# CarteMere.net
KiCad netlist of a schematic drawn in Altium Designer
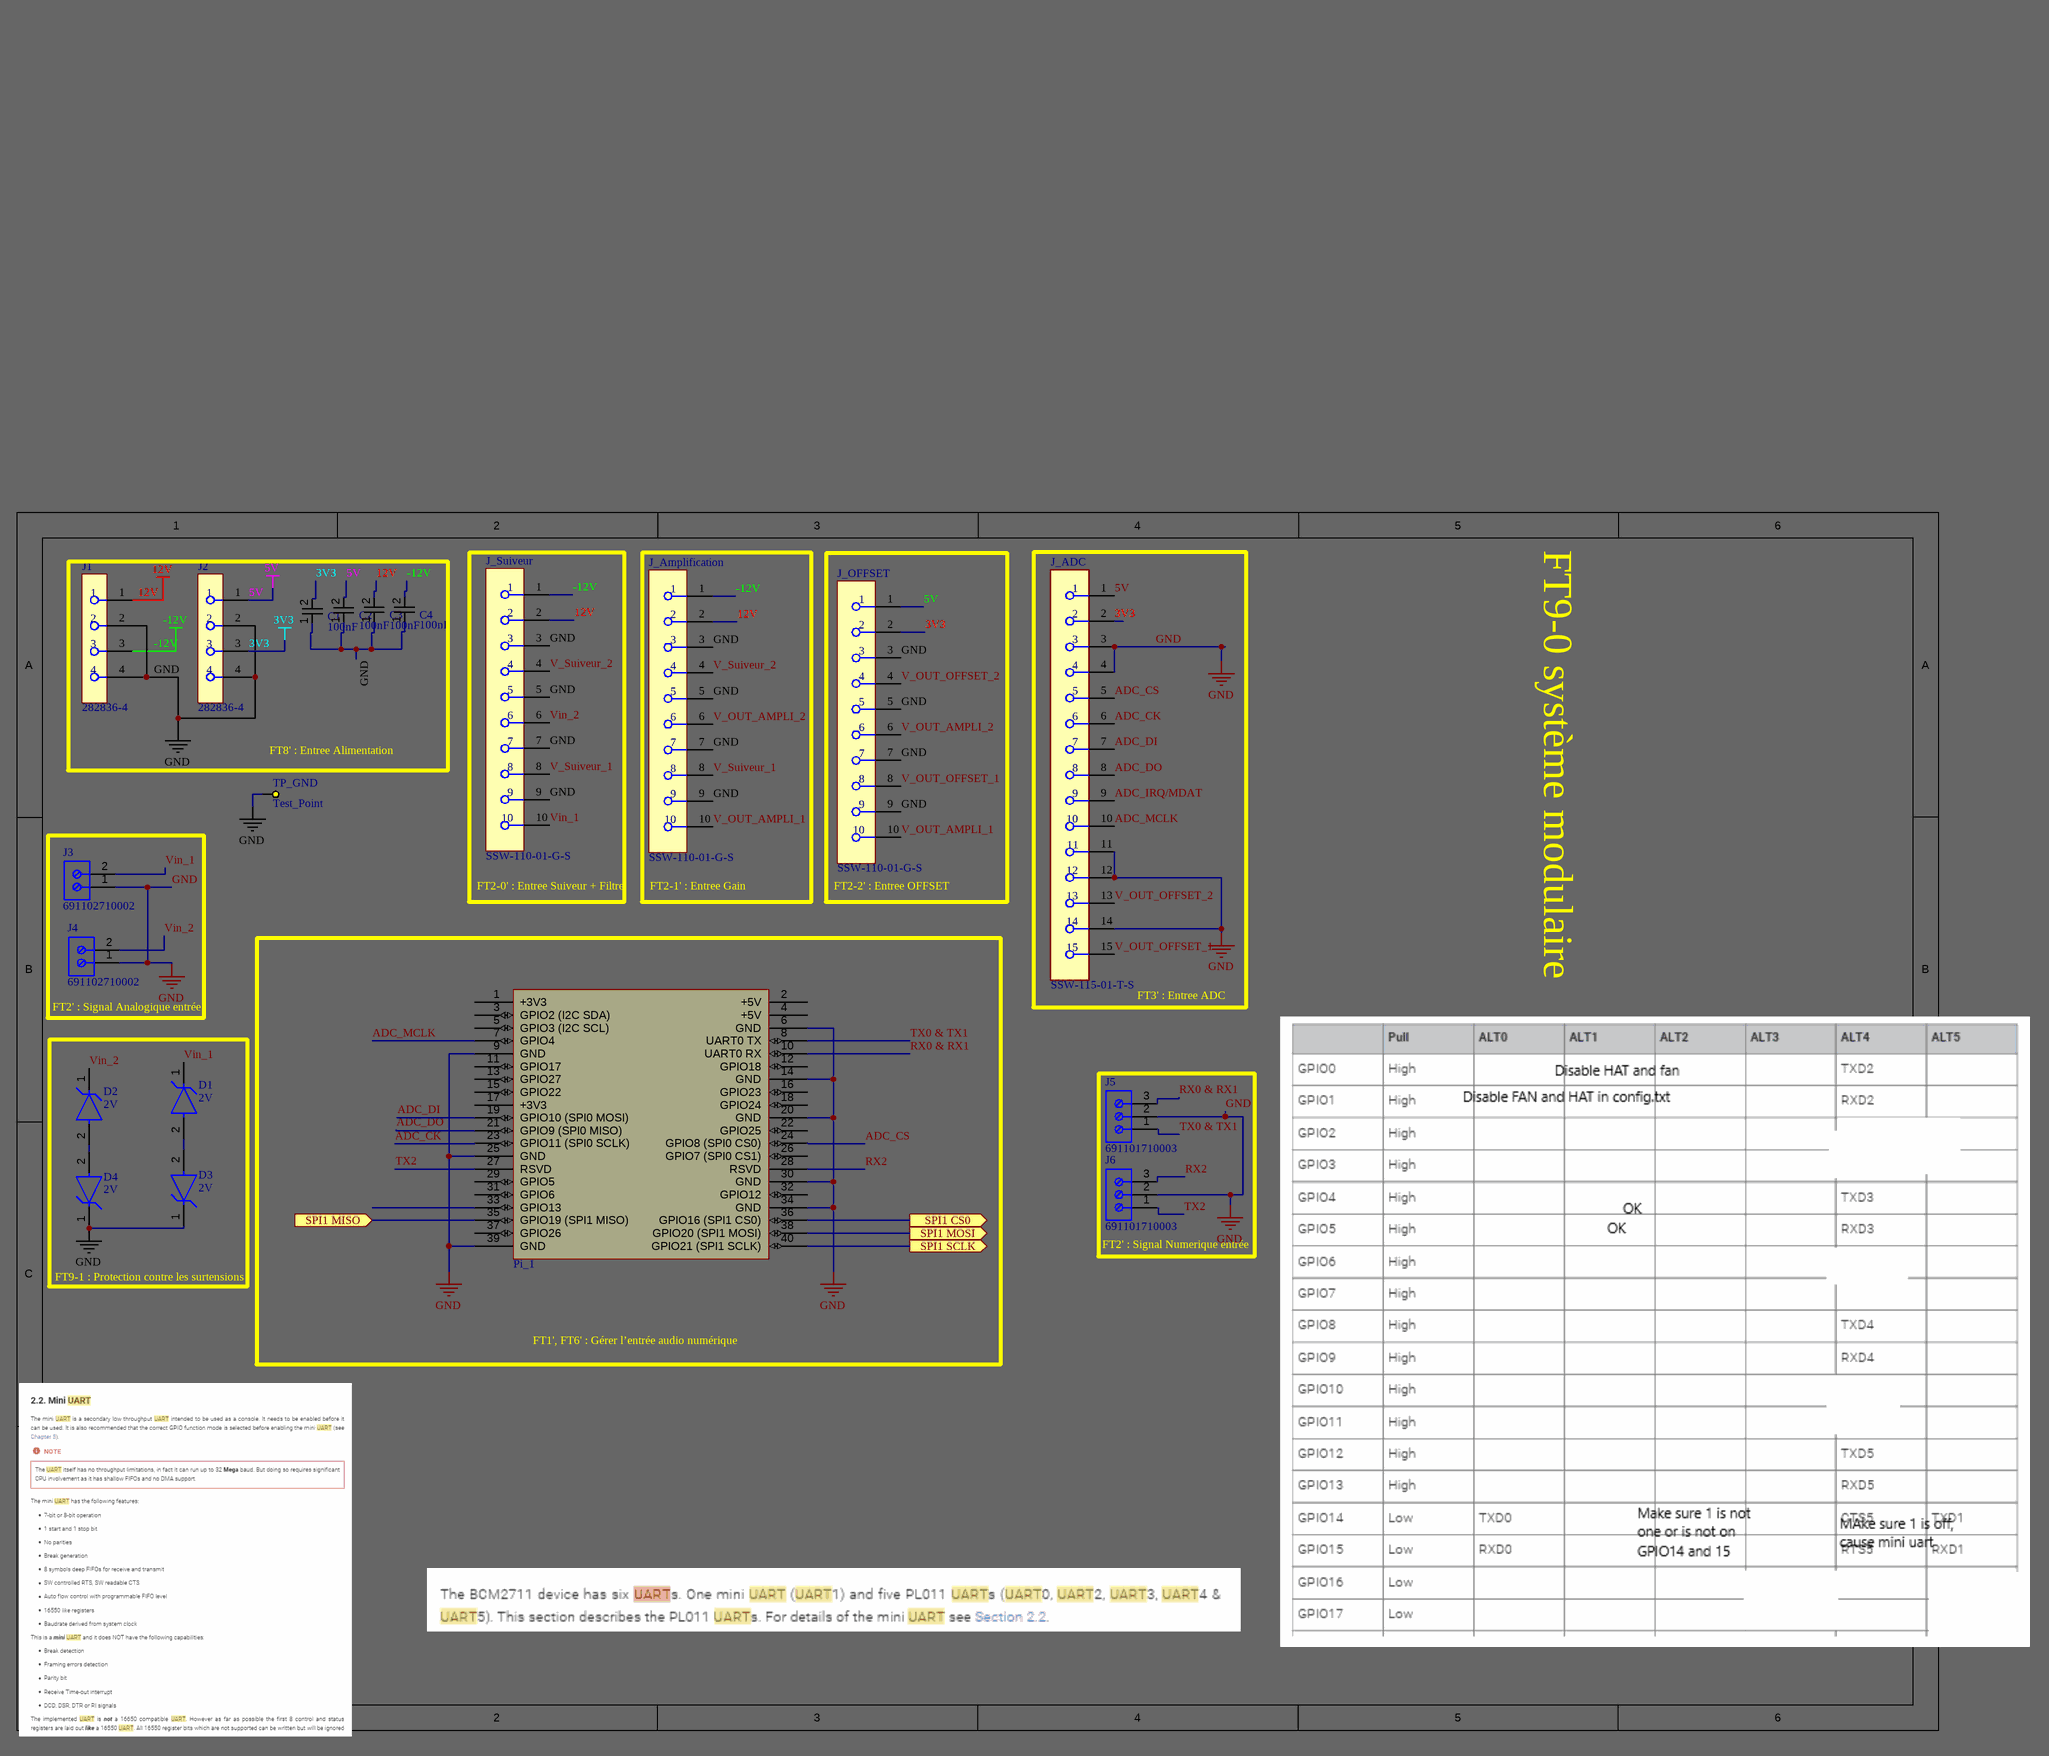
[diagram p0: CarteMere.SchDoc]

(export (version "E")
  (design (tool "Eeschema 10.0.6"))
  (components
    (comp (ref "C1")
      (value "100nF")
      (footprint "PCB:Cap_6.0%2A2.5%2A6mm")
      (fields (field (name "Comment") "Cap_6.0*2.5*6mm"))
      (libsource (lib "Schema") (part "Cap_6.0*2.5*6mm"))
    )
    (comp (ref "C2")
      (value "100nF")
      (footprint "PCB:Cap_6.0%2A2.5%2A6mm")
      (fields (field (name "Comment") "Cap_6.0*2.5*6mm"))
      (libsource (lib "Schema") (part "Cap_6.0*2.5*6mm"))
    )
    (comp (ref "C3")
      (value "100nF")
      (footprint "PCB:Cap_6.0%2A2.5%2A6mm")
      (fields (field (name "Comment") "Cap_6.0*2.5*6mm"))
      (libsource (lib "Schema") (part "Cap_6.0*2.5*6mm"))
    )
    (comp (ref "C4")
      (value "100nF")
      (footprint "PCB:Cap_6.0%2A2.5%2A6mm")
      (fields (field (name "Comment") "Cap_6.0*2.5*6mm"))
      (libsource (lib "Schema") (part "Cap_6.0*2.5*6mm"))
    )
    (comp (ref "D1")
      (value "2V")
      (footprint "PCB:Zener_Diode")
      (fields (field (name "Comment") "ZENER_Diode"))
      (libsource (lib "Schema") (part "ZENER_Diode"))
    )
    (comp (ref "D2")
      (value "2V")
      (footprint "PCB:Zener_Diode")
      (fields (field (name "Comment") "ZENER_Diode"))
      (libsource (lib "Schema") (part "ZENER_Diode"))
    )
    (comp (ref "D3")
      (value "2V")
      (footprint "PCB:Zener_Diode")
      (fields (field (name "Comment") "ZENER_Diode"))
      (libsource (lib "Schema") (part "ZENER_Diode"))
    )
    (comp (ref "D4")
      (value "2V")
      (footprint "PCB:Zener_Diode")
      (fields (field (name "Comment") "ZENER_Diode"))
      (libsource (lib "Schema") (part "ZENER_Diode"))
    )
    (comp (ref "J1")
      (value "282836-4")
      (footprint "FP-282836-4-MFG")
      (description "282836-4 Connector, Terminal Block; Wire Receptacle; 4 Pos.; 16-30 AWG; 0.197 in. CL; Sid")
      (fields (field (name "VOLTAGE") "300V"))
      (libsource (lib "Altium Content Vault") (part "282836-4"))
    )
    (comp (ref "J2")
      (value "282836-4")
      (footprint "FP-282836-4-MFG")
      (description "282836-4 Connector, Terminal Block; Wire Receptacle; 4 Pos.; 16-30 AWG; 0.197 in. CL; Sid")
      (fields (field (name "VOLTAGE") "300V"))
      (libsource (lib "Altium Content Vault") (part "282836-4"))
    )
    (comp (ref "J3")
      (value "691102710002")
      (footprint "691102710002")
      (fields (field (name "VOLTAGE") "300V"))
      (libsource (lib "Altium Content Vault") (part "TBL - 1R - 02P - Screw"))
    )
    (comp (ref "J4")
      (value "691102710002")
      (footprint "691102710002")
      (fields (field (name "VOLTAGE") "300V"))
      (libsource (lib "") (part "TBL - 1R - 02P - Screw_1"))
    )
    (comp (ref "J5")
      (value "691101710003")
      (footprint "691101710003")
      (fields (field (name "VOLTAGE") "250V"))
      (libsource (lib "Altium Content Vault") (part "TBL - 1R - 03P - Screw"))
    )
    (comp (ref "J6")
      (value "691101710003")
      (footprint "691101710003")
      (fields (field (name "VOLTAGE") "250V"))
      (libsource (lib "Altium Content Vault") (part "TBL - 1R - 03P - Screw"))
    )
    (comp (ref "J_ADC")
      (value "SSW-115-01-T-S")
      (footprint "FP-SSW-115-01-T-S-MFG")
      (description "CONN RCPT 15POS 0.1 TIN PCB")
      (libsource (lib "Altium Content Vault") (part "de2cdd76613f87adcba81301aaab7e9"))
    )
    (comp (ref "J_Amplification")
      (value "SSW-110-01-G-S")
      (footprint "FP-SSW-110-01-G-S-MFG")
      (libsource (lib "Altium Content Vault") (part "a6b0ccc4a6f32c6729440d11cede569"))
    )
    (comp (ref "J_OFFSET")
      (value "SSW-110-01-G-S")
      (footprint "FP-SSW-110-01-G-S-MFG")
      (libsource (lib "Altium Content Vault") (part "a6b0ccc4a6f32c6729440d11cede569"))
    )
    (comp (ref "J_Suiveur")
      (value "SSW-110-01-G-S")
      (footprint "FP-SSW-110-01-G-S-MFG")
      (libsource (lib "Altium Content Vault") (part "a6b0ccc4a6f32c6729440d11cede569"))
    )
    (comp (ref "Pi_1")
      (value "GPIO_conn_RaspberyPi")
      (footprint "PCB:Pi_20x2_pins_Male")
      (libsource (lib "Schema") (part "GPIO_conn_RaspberyPi"))
    )
    (comp (ref "TP_GND")
      (value "Test_Point")
      (footprint "PCB:Test_Point_Hook")
      (libsource (lib "Schema") (part "Test_Point"))
    )
  )
  (nets
    (net (code "1") (name "-12V") (class "Default")
      (node (ref "C4") (pin "2") (pinfunction "2_2") (pintype "passive"))
      (node (ref "J1") (pin "3") (pinfunction "3_3") (pintype "passive"))
      (node (ref "J_Amplification") (pin "1") (pinfunction "1_1") (pintype "passive"))
      (node (ref "J_Suiveur") (pin "1") (pinfunction "1_1") (pintype "passive"))
    )
    (net (code "3") (name "/ADC_CK") (class "Default")
      (node (ref "J_ADC") (pin "6") (pinfunction "6_6") (pintype "passive"))
      (node (ref "Pi_1") (pin "23") (pinfunction "GPIO11_(SPI0_SCLK)_23") (pintype "bidirectional"))
    )
    (net (code "4") (name "/ADC_CS") (class "Default")
      (node (ref "J_ADC") (pin "5") (pinfunction "5_5") (pintype "passive"))
      (node (ref "Pi_1") (pin "24") (pinfunction "GPIO8_(SPI0_CS0)_24") (pintype "bidirectional"))
    )
    (net (code "5") (name "/ADC_DI") (class "Default")
      (node (ref "J_ADC") (pin "7") (pinfunction "7_7") (pintype "passive"))
      (node (ref "Pi_1") (pin "19") (pinfunction "GPIO10_(SPI0_MOSI)_19") (pintype "bidirectional"))
    )
    (net (code "6") (name "/ADC_DO") (class "Default")
      (node (ref "J_ADC") (pin "8") (pinfunction "8_8") (pintype "passive"))
      (node (ref "Pi_1") (pin "21") (pinfunction "GPIO9_(SPI0_MISO)_21") (pintype "bidirectional"))
    )
    (net (code "7") (name "/ADC_IRQ{slash}MDAT") (class "Default")
      (node (ref "J_ADC") (pin "9") (pinfunction "9_9") (pintype "passive"))
    )
    (net (code "8") (name "/ADC_MCLK") (class "Default")
      (node (ref "J_ADC") (pin "10") (pinfunction "10_10") (pintype "passive"))
      (node (ref "Pi_1") (pin "7") (pinfunction "GPIO4_7") (pintype "bidirectional"))
    )
    (net (code "9") (name "/RX0 & RX1") (class "Default")
      (node (ref "J5") (pin "3") (pinfunction "3_3") (pintype "passive"))
      (node (ref "Pi_1") (pin "10") (pinfunction "UART0_RX_10") (pintype "bidirectional"))
    )
    (net (code "10") (name "/RX2") (class "Default")
      (node (ref "J6") (pin "3") (pinfunction "3_3") (pintype "passive"))
      (node (ref "Pi_1") (pin "28") (pinfunction "RSVD_28") (pintype "passive"))
    )
    (net (code "11") (name "/SPI1 CS0") (class "Default")
      (node (ref "Pi_1") (pin "36") (pinfunction "GPIO16_(SPI1_CS0)_36") (pintype "bidirectional"))
    )
    (net (code "12") (name "/SPI1 MISO") (class "Default")
      (node (ref "Pi_1") (pin "35") (pinfunction "GPIO19_(SPI1_MISO)_35") (pintype "bidirectional"))
    )
    (net (code "13") (name "/SPI1 MOSI") (class "Default")
      (node (ref "Pi_1") (pin "38") (pinfunction "GPIO20_(SPI1_MOSI)_38") (pintype "bidirectional"))
    )
    (net (code "14") (name "/SPI1 SCLK") (class "Default")
      (node (ref "Pi_1") (pin "40") (pinfunction "GPIO21_(SPI1_SCLK)_40") (pintype "bidirectional"))
    )
    (net (code "15") (name "/TX0 & TX1") (class "Default")
      (node (ref "J5") (pin "1") (pinfunction "1_1") (pintype "passive"))
      (node (ref "Pi_1") (pin "8") (pinfunction "UART0_TX_8") (pintype "bidirectional"))
    )
    (net (code "16") (name "/TX2") (class "Default")
      (node (ref "J6") (pin "1") (pinfunction "1_1") (pintype "passive"))
      (node (ref "Pi_1") (pin "27") (pinfunction "RSVD_27") (pintype "passive"))
    )
    (net (code "17") (name "/V_OUT_AMPLI_1") (class "Default")
      (node (ref "J_Amplification") (pin "10") (pinfunction "10_10") (pintype "passive"))
      (node (ref "J_OFFSET") (pin "10") (pinfunction "10_10") (pintype "passive"))
    )
    (net (code "18") (name "/V_OUT_AMPLI_2") (class "Default")
      (node (ref "J_Amplification") (pin "6") (pinfunction "6_6") (pintype "passive"))
      (node (ref "J_OFFSET") (pin "6") (pinfunction "6_6") (pintype "passive"))
    )
    (net (code "19") (name "/V_OUT_OFFSET_1") (class "Default")
      (node (ref "J_ADC") (pin "15") (pinfunction "15_15") (pintype "passive"))
      (node (ref "J_OFFSET") (pin "8") (pinfunction "8_8") (pintype "passive"))
    )
    (net (code "20") (name "/V_OUT_OFFSET_2") (class "Default")
      (node (ref "J_ADC") (pin "13") (pinfunction "13_13") (pintype "passive"))
      (node (ref "J_OFFSET") (pin "4") (pinfunction "4_4") (pintype "passive"))
    )
    (net (code "21") (name "/V_Suiveur_1") (class "Default")
      (node (ref "J_Amplification") (pin "8") (pinfunction "8_8") (pintype "passive"))
      (node (ref "J_Suiveur") (pin "8") (pinfunction "8_8") (pintype "passive"))
    )
    (net (code "22") (name "/V_Suiveur_2") (class "Default")
      (node (ref "J_Amplification") (pin "4") (pinfunction "4_4") (pintype "passive"))
      (node (ref "J_Suiveur") (pin "4") (pinfunction "4_4") (pintype "passive"))
    )
    (net (code "23") (name "/Vin_1") (class "Default")
      (node (ref "D1") (pin "1") (pinfunction "C_1") (pintype "passive"))
      (node (ref "J3") (pin "2") (pinfunction "2_2") (pintype "passive"))
      (node (ref "J_Suiveur") (pin "10") (pinfunction "10_10") (pintype "passive"))
    )
    (net (code "24") (name "/Vin_2") (class "Default")
      (node (ref "D2") (pin "1") (pinfunction "C_1") (pintype "passive"))
      (node (ref "J4") (pin "2") (pinfunction "2_2") (pintype "passive"))
      (node (ref "J_Suiveur") (pin "6") (pinfunction "6_6") (pintype "passive"))
    )
    (net (code "25") (name "3V3") (class "Default")
      (node (ref "C1") (pin "2") (pinfunction "2_2") (pintype "passive"))
      (node (ref "J2") (pin "3") (pinfunction "3_3") (pintype "passive"))
      (node (ref "J_ADC") (pin "2") (pinfunction "2_2") (pintype "passive"))
      (node (ref "J_OFFSET") (pin "2") (pinfunction "2_2") (pintype "passive"))
    )
    (net (code "26") (name "5V") (class "Default")
      (node (ref "C2") (pin "2") (pinfunction "2_2") (pintype "passive"))
      (node (ref "J2") (pin "1") (pinfunction "1_1") (pintype "passive"))
      (node (ref "J_ADC") (pin "1") (pinfunction "1_1") (pintype "passive"))
      (node (ref "J_OFFSET") (pin "1") (pinfunction "1_1") (pintype "passive"))
    )
    (net (code "27") (name "12V") (class "Default")
      (node (ref "C3") (pin "2") (pinfunction "2_2") (pintype "passive"))
      (node (ref "J1") (pin "1") (pinfunction "1_1") (pintype "passive"))
      (node (ref "J_Amplification") (pin "2") (pinfunction "2_2") (pintype "passive"))
      (node (ref "J_Suiveur") (pin "2") (pinfunction "2_2") (pintype "passive"))
    )
    (net (code "28") (name "GND") (class "Default")
      (node (ref "C1") (pin "1") (pinfunction "1_1") (pintype "passive"))
      (node (ref "C2") (pin "1") (pinfunction "1_1") (pintype "passive"))
      (node (ref "C3") (pin "1") (pinfunction "1_1") (pintype "passive"))
      (node (ref "C4") (pin "1") (pinfunction "1_1") (pintype "passive"))
      (node (ref "D3") (pin "1") (pinfunction "C_1") (pintype "passive"))
      (node (ref "D4") (pin "1") (pinfunction "C_1") (pintype "passive"))
      (node (ref "J1") (pin "2") (pinfunction "2_2") (pintype "passive"))
      (node (ref "J1") (pin "4") (pinfunction "4_4") (pintype "passive"))
      (node (ref "J2") (pin "2") (pinfunction "2_2") (pintype "passive"))
      (node (ref "J2") (pin "4") (pinfunction "4_4") (pintype "passive"))
      (node (ref "J3") (pin "1") (pinfunction "1_1") (pintype "passive"))
      (node (ref "J4") (pin "1") (pinfunction "1_1") (pintype "passive"))
      (node (ref "J5") (pin "2") (pinfunction "2_2") (pintype "passive"))
      (node (ref "J6") (pin "2") (pinfunction "2_2") (pintype "passive"))
      (node (ref "J_ADC") (pin "11") (pinfunction "11_11") (pintype "passive"))
      (node (ref "J_ADC") (pin "12") (pinfunction "12_12") (pintype "passive"))
      (node (ref "J_ADC") (pin "14") (pinfunction "14_14") (pintype "passive"))
      (node (ref "J_ADC") (pin "3") (pinfunction "3_3") (pintype "passive"))
      (node (ref "J_ADC") (pin "4") (pinfunction "4_4") (pintype "passive"))
      (node (ref "J_Amplification") (pin "3") (pinfunction "3_3") (pintype "passive"))
      (node (ref "J_Amplification") (pin "5") (pinfunction "5_5") (pintype "passive"))
      (node (ref "J_Amplification") (pin "7") (pinfunction "7_7") (pintype "passive"))
      (node (ref "J_Amplification") (pin "9") (pinfunction "9_9") (pintype "passive"))
      (node (ref "J_OFFSET") (pin "3") (pinfunction "3_3") (pintype "passive"))
      (node (ref "J_OFFSET") (pin "5") (pinfunction "5_5") (pintype "passive"))
      (node (ref "J_OFFSET") (pin "7") (pinfunction "7_7") (pintype "passive"))
      (node (ref "J_OFFSET") (pin "9") (pinfunction "9_9") (pintype "passive"))
      (node (ref "J_Suiveur") (pin "3") (pinfunction "3_3") (pintype "passive"))
      (node (ref "J_Suiveur") (pin "5") (pinfunction "5_5") (pintype "passive"))
      (node (ref "J_Suiveur") (pin "7") (pinfunction "7_7") (pintype "passive"))
      (node (ref "J_Suiveur") (pin "9") (pinfunction "9_9") (pintype "passive"))
      (node (ref "Pi_1") (pin "14") (pinfunction "GND_14") (pintype "power_in"))
      (node (ref "Pi_1") (pin "20") (pinfunction "GND_20") (pintype "power_in"))
      (node (ref "Pi_1") (pin "25") (pinfunction "GND_25") (pintype "power_in"))
      (node (ref "Pi_1") (pin "30") (pinfunction "GND_30") (pintype "power_in"))
      (node (ref "Pi_1") (pin "34") (pinfunction "GND_34") (pintype "passive"))
      (node (ref "Pi_1") (pin "39") (pinfunction "GND_39") (pintype "power_in"))
      (node (ref "Pi_1") (pin "6") (pinfunction "GND_6") (pintype "power_in"))
      (node (ref "Pi_1") (pin "9") (pinfunction "GND_9") (pintype "power_in"))
      (node (ref "TP_GND") (pin "Tp?") (pinfunction "0_Tp?") (pintype "passive"))
    )
    (net (code "29") (name "Net-(D1-A)") (class "Default")
      (node (ref "D1") (pin "2") (pinfunction "A_2") (pintype "passive"))
      (node (ref "D3") (pin "2") (pinfunction "A_2") (pintype "passive"))
    )
    (net (code "30") (name "Net-(D2-A)") (class "Default")
      (node (ref "D2") (pin "2") (pinfunction "A_2") (pintype "passive"))
      (node (ref "D4") (pin "2") (pinfunction "A_2") (pintype "passive"))
    )
    (net (code "31") (name "unconnected-(Pi_1-+3V3-Pad1)") (class "Default")
      (node (ref "Pi_1") (pin "1") (pinfunction "+3V3_1") (pintype "power_in"))
    )
    (net (code "32") (name "unconnected-(Pi_1-+3V3-Pad17)") (class "Default")
      (node (ref "Pi_1") (pin "17") (pinfunction "+3V3_17") (pintype "power_in"))
    )
    (net (code "33") (name "unconnected-(Pi_1-+5V-Pad2)") (class "Default")
      (node (ref "Pi_1") (pin "2") (pinfunction "+5V_2") (pintype "power_in"))
    )
    (net (code "34") (name "unconnected-(Pi_1-+5V-Pad4)") (class "Default")
      (node (ref "Pi_1") (pin "4") (pinfunction "+5V_4") (pintype "power_in"))
    )
    (net (code "35") (name "unconnected-(Pi_1-GPIO2_(I2C_SDA)-Pad3)") (class "Default")
      (node (ref "Pi_1") (pin "3") (pinfunction "GPIO2_(I2C_SDA)_3") (pintype "bidirectional"))
    )
    (net (code "36") (name "unconnected-(Pi_1-GPIO3_(I2C_SCL)-Pad5)") (class "Default")
      (node (ref "Pi_1") (pin "5") (pinfunction "GPIO3_(I2C_SCL)_5") (pintype "bidirectional"))
    )
    (net (code "37") (name "unconnected-(Pi_1-GPIO5-Pad29)") (class "Default")
      (node (ref "Pi_1") (pin "29") (pinfunction "GPIO5_29") (pintype "bidirectional"))
    )
    (net (code "38") (name "unconnected-(Pi_1-GPIO6-Pad31)") (class "Default")
      (node (ref "Pi_1") (pin "31") (pinfunction "GPIO6_31") (pintype "bidirectional"))
    )
    (net (code "39") (name "unconnected-(Pi_1-GPIO7_(SPI0_CS1)-Pad26)") (class "Default")
      (node (ref "Pi_1") (pin "26") (pinfunction "GPIO7_(SPI0_CS1)_26") (pintype "bidirectional"))
    )
    (net (code "40") (name "unconnected-(Pi_1-GPIO12-Pad32)") (class "Default")
      (node (ref "Pi_1") (pin "32") (pinfunction "GPIO12_32") (pintype "bidirectional"))
    )
    (net (code "41") (name "unconnected-(Pi_1-GPIO13-Pad33)") (class "Default")
      (node (ref "Pi_1") (pin "33") (pinfunction "GPIO13_33") (pintype "bidirectional"))
    )
    (net (code "42") (name "unconnected-(Pi_1-GPIO17-Pad11)") (class "Default")
      (node (ref "Pi_1") (pin "11") (pinfunction "GPIO17_11") (pintype "bidirectional"))
    )
    (net (code "43") (name "unconnected-(Pi_1-GPIO18-Pad12)") (class "Default")
      (node (ref "Pi_1") (pin "12") (pinfunction "GPIO18_12") (pintype "bidirectional"))
    )
    (net (code "44") (name "unconnected-(Pi_1-GPIO22-Pad15)") (class "Default")
      (node (ref "Pi_1") (pin "15") (pinfunction "GPIO22_15") (pintype "bidirectional"))
    )
    (net (code "45") (name "unconnected-(Pi_1-GPIO23-Pad16)") (class "Default")
      (node (ref "Pi_1") (pin "16") (pinfunction "GPIO23_16") (pintype "bidirectional"))
    )
    (net (code "46") (name "unconnected-(Pi_1-GPIO24-Pad18)") (class "Default")
      (node (ref "Pi_1") (pin "18") (pinfunction "GPIO24_18") (pintype "bidirectional"))
    )
    (net (code "47") (name "unconnected-(Pi_1-GPIO25-Pad22)") (class "Default")
      (node (ref "Pi_1") (pin "22") (pinfunction "GPIO25_22") (pintype "bidirectional"))
    )
    (net (code "48") (name "unconnected-(Pi_1-GPIO26-Pad37)") (class "Default")
      (node (ref "Pi_1") (pin "37") (pinfunction "GPIO26_37") (pintype "bidirectional"))
    )
    (net (code "49") (name "unconnected-(Pi_1-GPIO27-Pad13)") (class "Default")
      (node (ref "Pi_1") (pin "13") (pinfunction "GPIO27_13") (pintype "bidirectional"))
    )
  )
)
